# SCH_Orcon_MV_Control.net
KiCad netlist of a schematic drawn in EasyEDA
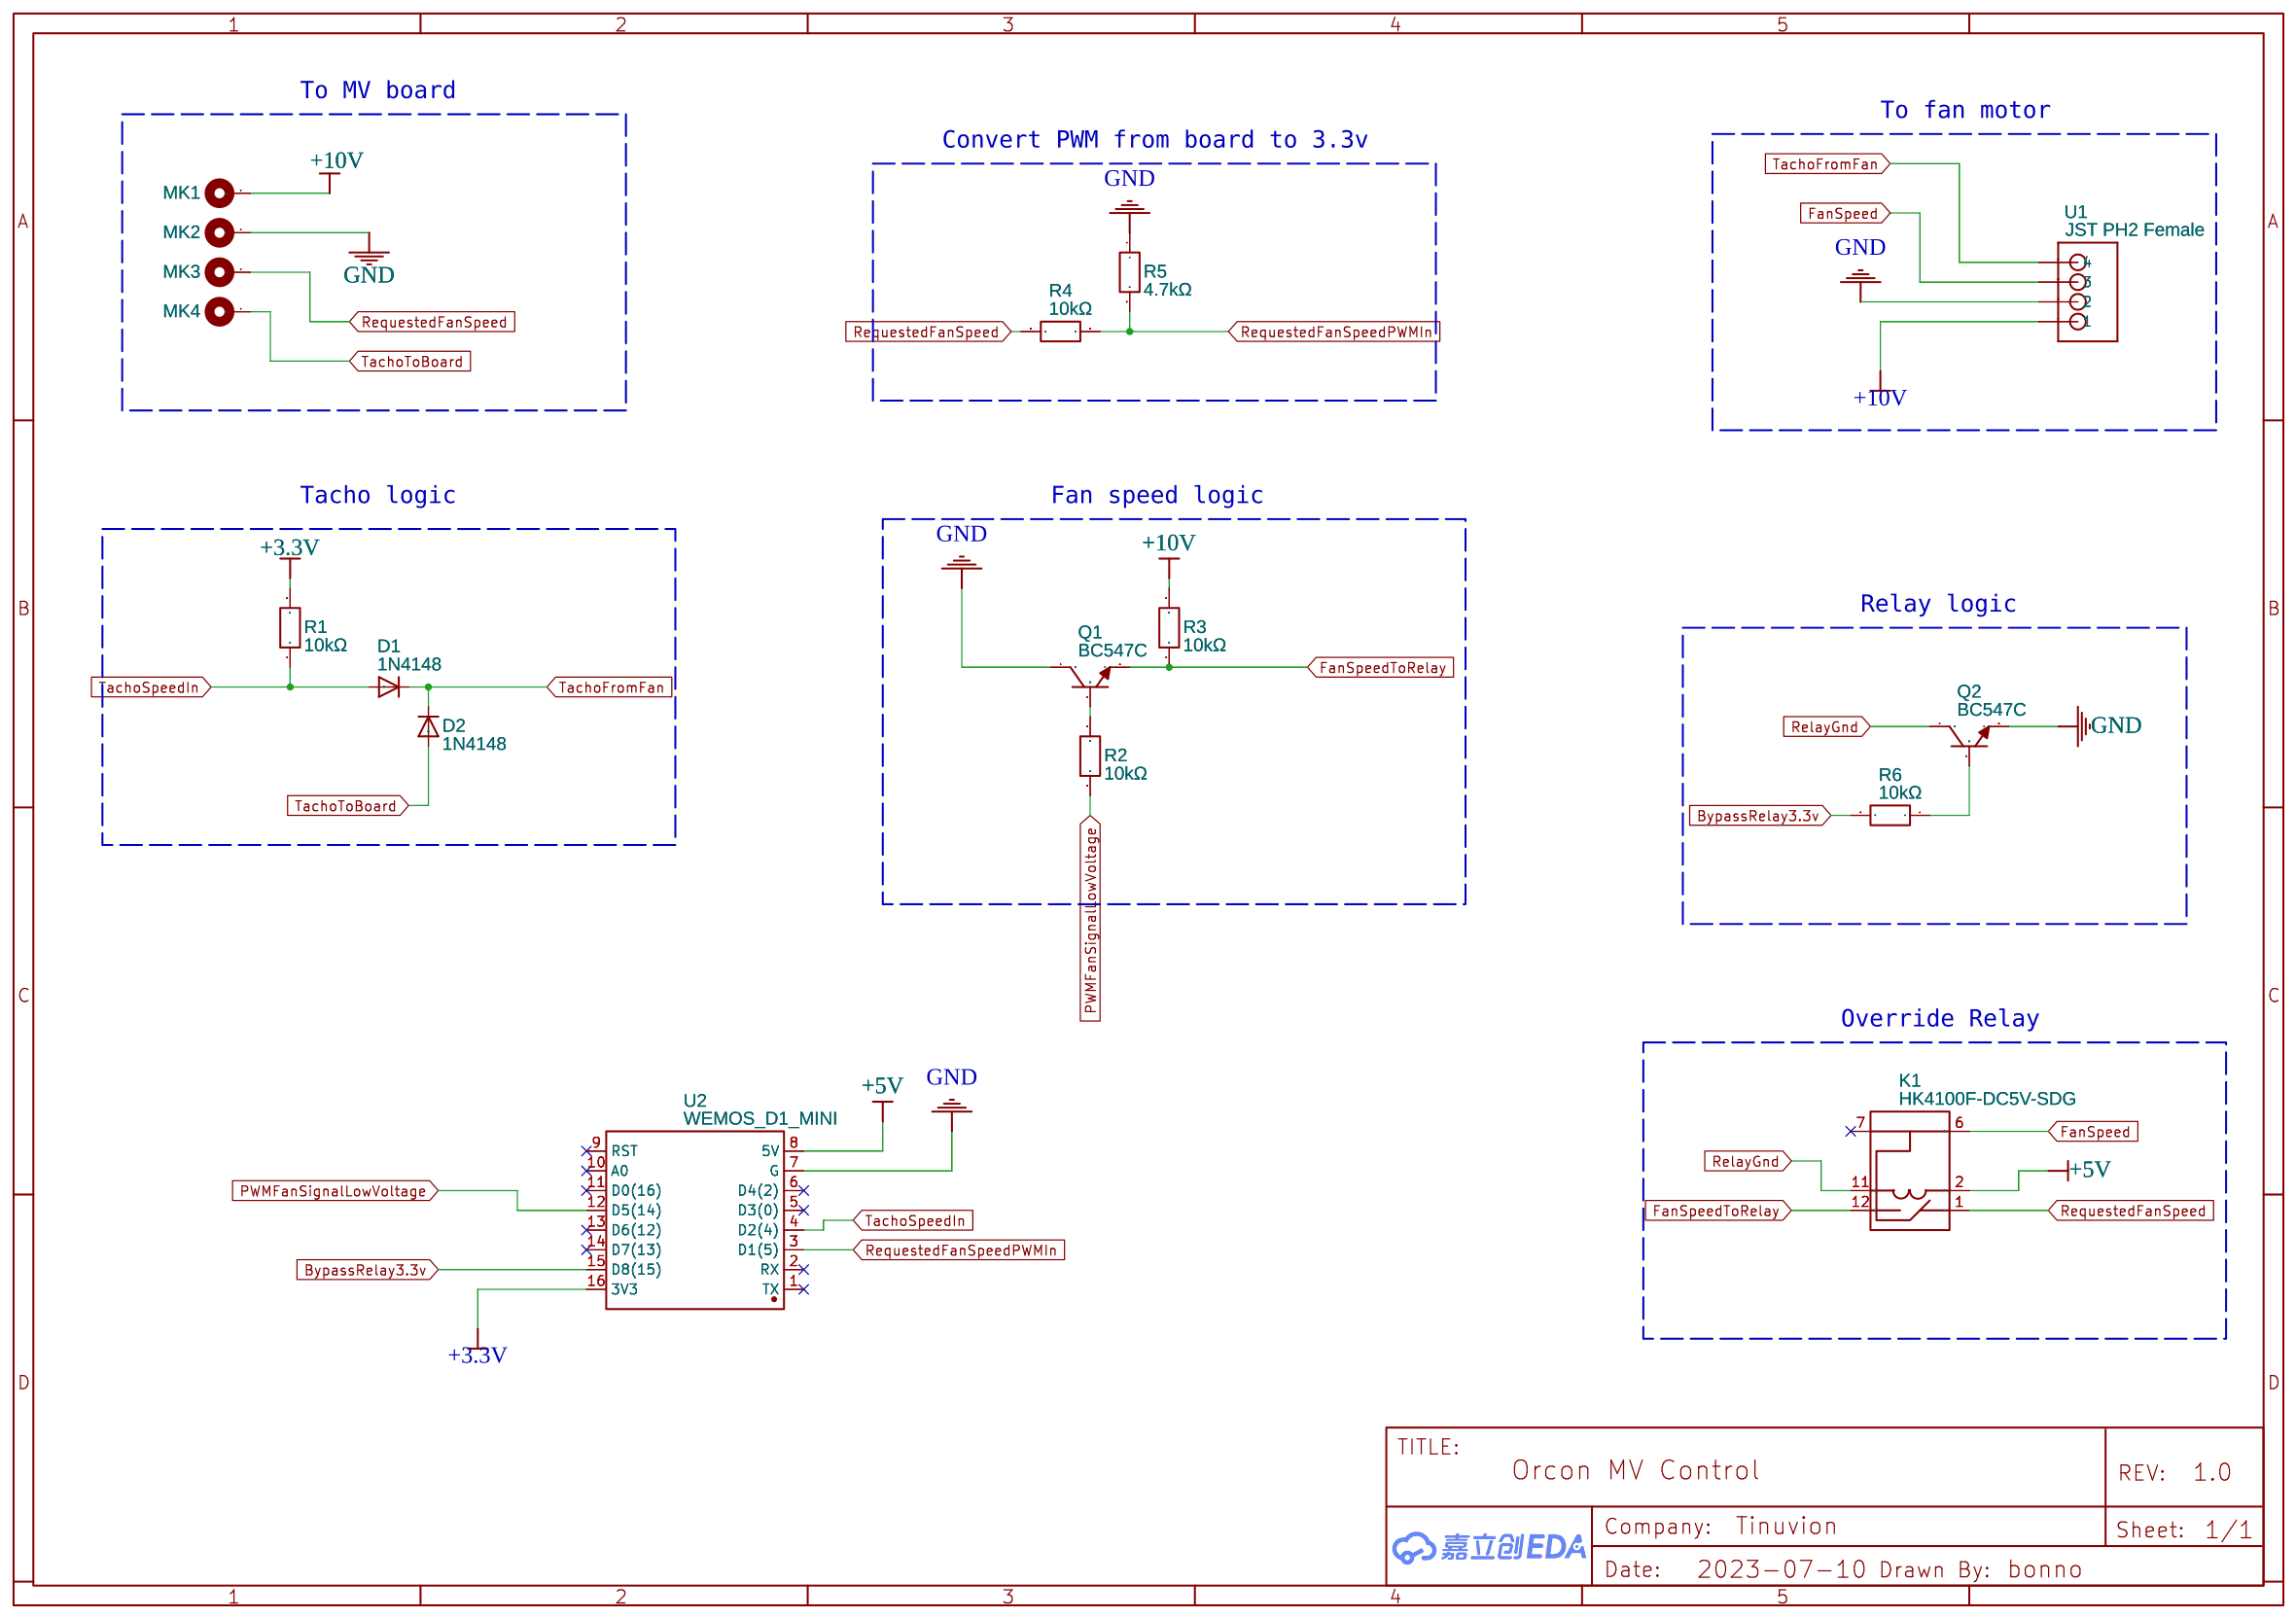
[diagram p0: schematic sheet]

(export (version "E")
  (design (tool "Eeschema 10.0.6"))
  (components
    (comp (ref "D1")
      (value "1N4148")
      (fields (field (name "Manufacturer") "ST(先科)"))
      (libsource (lib "") (part "DIODE"))
    )
    (comp (ref "D2")
      (value "1N4148")
      (fields (field (name "Manufacturer") "ST(先科)"))
      (libsource (lib "") (part "DIODE_1"))
    )
    (comp (ref "K1")
      (value "HK4100F-DC5V-SDG")
      (fields (field (name "Manufacturer") "汇科"))
      (libsource (lib "") (part "HK4100F-DC5V-SDG"))
    )
    (comp (ref "MK1") (value "Mounting_Hole_PAD") (libsource (lib "") (part "Mounting_Hole_PAD")))
    (comp (ref "MK2") (value "Mounting_Hole_PAD") (libsource (lib "") (part "Mounting_Hole_PAD")))
    (comp (ref "MK3") (value "Mounting_Hole_PAD") (libsource (lib "") (part "Mounting_Hole_PAD")))
    (comp (ref "MK4") (value "Mounting_Hole_PAD") (libsource (lib "") (part "Mounting_Hole_PAD")))
    (comp (ref "Q1")
      (value "BC547C")
      (fields (field (name "Manufacturer") "LGE"))
      (libsource (lib "") (part "BC547C"))
    )
    (comp (ref "Q2")
      (value "BC547C")
      (fields (field (name "Manufacturer") "LGE"))
      (libsource (lib "") (part "BC547C"))
    )
    (comp (ref "R1")
      (value "10kΩ")
      (fields (field (name "Manufacturer Part") "AR03BTD1002") (field (name "Manufacturer") "Viking(光颉)"))
      (libsource (lib "") (part "R_0603_EU_2"))
    )
    (comp (ref "R2")
      (value "10kΩ")
      (fields (field (name "Manufacturer Part") "AR03BTD1002") (field (name "Manufacturer") "Viking(光颉)"))
      (libsource (lib "") (part "R_0603_EU_2"))
    )
    (comp (ref "R3")
      (value "10kΩ")
      (fields (field (name "Manufacturer Part") "AR03BTD1002") (field (name "Manufacturer") "Viking(光颉)"))
      (libsource (lib "") (part "R_0603_EU_2"))
    )
    (comp (ref "R4")
      (value "10kΩ")
      (fields (field (name "Manufacturer Part") "AR03BTD1002") (field (name "Manufacturer") "Viking(光颉)"))
      (libsource (lib "") (part "R_0603_EU_1"))
    )
    (comp (ref "R5")
      (value "4.7kΩ")
      (fields (field (name "Manufacturer Part") "AR03DTCX4701") (field (name "Manufacturer") "Viking(光颉)"))
      (libsource (lib "") (part "R_0603_EU"))
    )
    (comp (ref "R6")
      (value "10kΩ")
      (fields (field (name "Manufacturer Part") "AR03BTD1002") (field (name "Manufacturer") "Viking(光颉)"))
      (libsource (lib "") (part "R_0603_EU_1"))
    )
    (comp (ref "U1") (value "JST PH2 Female") (libsource (lib "") (part "JST-PH_4-PIN_HEADER")))
    (comp (ref "U2")
      (value "WEMOS_D1_MINI")
      (fields (field (name "Manufacturer Part") "Wemos_D1_mini_Pro4"))
      (libsource (lib "") (part "WEMOS_D1_MINI_PRO4"))
    )
  )
  (nets
    (net (code "1") (name "+3.3V") (class "Default")
      (node (ref "R1") (pin "2") (pinfunction "2_2") (pintype "unspecified"))
      (node (ref "U2") (pin "16") (pinfunction "3V3_16") (pintype "unspecified"))
    )
    (net (code "2") (name "+5V") (class "Default")
      (node (ref "K1") (pin "2") (pinfunction "2_2") (pintype "unspecified"))
      (node (ref "U2") (pin "8") (pinfunction "5V_8") (pintype "unspecified"))
    )
    (net (code "3") (name "+10V") (class "Default")
      (node (ref "MK1") (pin "1") (pinfunction "1_1") (pintype "input"))
      (node (ref "R3") (pin "2") (pinfunction "2_2") (pintype "unspecified"))
      (node (ref "U1") (pin "P1") (pinfunction "1_P1") (pintype "unspecified"))
    )
    (net (code "4") (name "BypassRelay3.3v") (class "Default")
      (node (ref "R6") (pin "2") (pinfunction "2_2") (pintype "unspecified"))
      (node (ref "U2") (pin "15") (pinfunction "D8(15)_15") (pintype "unspecified"))
    )
    (net (code "5") (name "FanSpeed") (class "Default")
      (node (ref "K1") (pin "6") (pinfunction "6_6") (pintype "unspecified"))
      (node (ref "U1") (pin "P3") (pinfunction "3_P3") (pintype "unspecified"))
    )
    (net (code "6") (name "FanSpeedToRelay") (class "Default")
      (node (ref "K1") (pin "12") (pinfunction "12_12") (pintype "unspecified"))
      (node (ref "Q1") (pin "3") (pinfunction "E_3") (pintype "input"))
      (node (ref "R3") (pin "1") (pinfunction "1_1") (pintype "unspecified"))
    )
    (net (code "7") (name "GND") (class "Default")
      (node (ref "MK2") (pin "1") (pinfunction "1_1") (pintype "input"))
      (node (ref "Q1") (pin "1") (pinfunction "C_1") (pintype "input"))
      (node (ref "Q2") (pin "3") (pinfunction "E_3") (pintype "input"))
      (node (ref "R5") (pin "1") (pinfunction "1_1") (pintype "unspecified"))
      (node (ref "U1") (pin "P2") (pinfunction "2_P2") (pintype "unspecified"))
      (node (ref "U2") (pin "7") (pinfunction "G_7") (pintype "unspecified"))
    )
    (net (code "8") (name "Net-(Q1-B)") (class "Default")
      (node (ref "Q1") (pin "2") (pinfunction "B_2") (pintype "input"))
      (node (ref "R2") (pin "2") (pinfunction "2_2") (pintype "unspecified"))
    )
    (net (code "9") (name "Net-(Q2-B)") (class "Default")
      (node (ref "Q2") (pin "2") (pinfunction "B_2") (pintype "input"))
      (node (ref "R6") (pin "1") (pinfunction "1_1") (pintype "unspecified"))
    )
    (net (code "10") (name "PWMFanSignalLowVoltage") (class "Default")
      (node (ref "R2") (pin "1") (pinfunction "1_1") (pintype "unspecified"))
      (node (ref "U2") (pin "12") (pinfunction "D5(14)_12") (pintype "unspecified"))
    )
    (net (code "11") (name "RelayGnd") (class "Default")
      (node (ref "K1") (pin "11") (pinfunction "11_11") (pintype "unspecified"))
      (node (ref "Q2") (pin "1") (pinfunction "C_1") (pintype "input"))
    )
    (net (code "12") (name "RequestedFanSpeed") (class "Default")
      (node (ref "K1") (pin "1") (pinfunction "1_1") (pintype "unspecified"))
      (node (ref "MK3") (pin "1") (pinfunction "1_1") (pintype "input"))
      (node (ref "R4") (pin "2") (pinfunction "2_2") (pintype "unspecified"))
    )
    (net (code "13") (name "RequestedFanSpeedPWMIn") (class "Default")
      (node (ref "R4") (pin "1") (pinfunction "1_1") (pintype "unspecified"))
      (node (ref "R5") (pin "2") (pinfunction "2_2") (pintype "unspecified"))
      (node (ref "U2") (pin "3") (pinfunction "D1(5)_3") (pintype "unspecified"))
    )
    (net (code "14") (name "TachoFromFan") (class "Default")
      (node (ref "D1") (pin "C") (pinfunction "C_C") (pintype "unspecified"))
      (node (ref "D2") (pin "C") (pinfunction "C_C") (pintype "unspecified"))
      (node (ref "U1") (pin "P4") (pinfunction "4_P4") (pintype "unspecified"))
    )
    (net (code "15") (name "TachoSpeedIn") (class "Default")
      (node (ref "D1") (pin "A") (pinfunction "A_A") (pintype "unspecified"))
      (node (ref "R1") (pin "1") (pinfunction "1_1") (pintype "unspecified"))
      (node (ref "U2") (pin "4") (pinfunction "D2(4)_4") (pintype "unspecified"))
    )
    (net (code "16") (name "TachoToBoard") (class "Default")
      (node (ref "D2") (pin "A") (pinfunction "A_A") (pintype "unspecified"))
      (node (ref "MK4") (pin "1") (pinfunction "1_1") (pintype "input"))
    )
    (net (code "17") (name "unconnected-(K1-Pad7)") (class "Default")
      (node (ref "K1") (pin "7") (pinfunction "7_7") (pintype "unspecified+no_connect"))
    )
    (net (code "18") (name "unconnected-(U2-A0-Pad10)") (class "Default")
      (node (ref "U2") (pin "10") (pinfunction "A0_10") (pintype "unspecified+no_connect"))
    )
    (net (code "19") (name "unconnected-(U2-D0(16)-Pad11)") (class "Default")
      (node (ref "U2") (pin "11") (pinfunction "D0(16)_11") (pintype "unspecified+no_connect"))
    )
    (net (code "20") (name "unconnected-(U2-D3(0)-Pad5)") (class "Default")
      (node (ref "U2") (pin "5") (pinfunction "D3(0)_5") (pintype "unspecified+no_connect"))
    )
    (net (code "21") (name "unconnected-(U2-D4(2)-Pad6)") (class "Default")
      (node (ref "U2") (pin "6") (pinfunction "D4(2)_6") (pintype "unspecified+no_connect"))
    )
    (net (code "22") (name "unconnected-(U2-D6(12)-Pad13)") (class "Default")
      (node (ref "U2") (pin "13") (pinfunction "D6(12)_13") (pintype "unspecified+no_connect"))
    )
    (net (code "23") (name "unconnected-(U2-D7(13)-Pad14)") (class "Default")
      (node (ref "U2") (pin "14") (pinfunction "D7(13)_14") (pintype "unspecified+no_connect"))
    )
    (net (code "24") (name "unconnected-(U2-RST-Pad9)") (class "Default")
      (node (ref "U2") (pin "9") (pinfunction "RST_9") (pintype "unspecified+no_connect"))
    )
    (net (code "25") (name "unconnected-(U2-RX-Pad2)") (class "Default")
      (node (ref "U2") (pin "2") (pinfunction "RX_2") (pintype "unspecified+no_connect"))
    )
    (net (code "26") (name "unconnected-(U2-TX-Pad1)") (class "Default")
      (node (ref "U2") (pin "1") (pinfunction "TX_1") (pintype "unspecified+no_connect"))
    )
  )
)
